# playA.net
KiCad netlist of a schematic drawn in Altium Designer
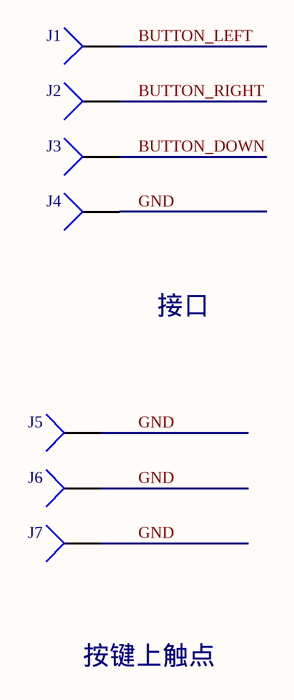
[diagram p0: playA.SchDoc]

(export (version "E")
  (design (tool "Eeschema 10.0.6"))
  (components
    (comp (ref "J1")
      (value "PAD")
      (footprint "LINK_PAD")
      (description "Socket")
      (fields (field (name "PUBLISHER") "Altium Limited"))
      (libsource (lib "Miscellaneous Connectors") (part "Socket"))
    )
    (comp (ref "J2")
      (value "PAD")
      (footprint "LINK_PAD")
      (description "Socket")
      (fields (field (name "PUBLISHER") "Altium Limited"))
      (libsource (lib "Miscellaneous Connectors") (part "Socket"))
    )
    (comp (ref "J3")
      (value "PAD")
      (footprint "LINK_PAD")
      (description "Socket")
      (fields (field (name "PUBLISHER") "Altium Limited"))
      (libsource (lib "Miscellaneous Connectors") (part "Socket"))
    )
    (comp (ref "J4")
      (value "PAD")
      (footprint "LINK_PAD")
      (description "Socket")
      (fields (field (name "PUBLISHER") "Altium Limited"))
      (libsource (lib "Miscellaneous Connectors") (part "Socket"))
    )
    (comp (ref "J5")
      (value "PAD")
      (footprint "Button_Pad")
      (description "Socket")
      (fields (field (name "PUBLISHER") "Altium Limited"))
      (libsource (lib "Miscellaneous Connectors") (part "Socket"))
    )
    (comp (ref "J6")
      (value "PAD")
      (footprint "Button_Pad")
      (description "Socket")
      (fields (field (name "PUBLISHER") "Altium Limited"))
      (libsource (lib "Miscellaneous Connectors") (part "Socket"))
    )
    (comp (ref "J7")
      (value "PAD")
      (footprint "Button_Pad")
      (description "Socket")
      (fields (field (name "PUBLISHER") "Altium Limited"))
      (libsource (lib "Miscellaneous Connectors") (part "Socket"))
    )
  )
  (nets
    (net (code "1") (name "/BUTTON_DOWN") (class "Default")
      (node (ref "J3") (pin "1") (pinfunction "1_1") (pintype "passive"))
    )
    (net (code "2") (name "/BUTTON_LEFT") (class "Default")
      (node (ref "J1") (pin "1") (pinfunction "1_1") (pintype "passive"))
    )
    (net (code "3") (name "/BUTTON_RIGHT") (class "Default")
      (node (ref "J2") (pin "1") (pinfunction "1_1") (pintype "passive"))
    )
    (net (code "4") (name "/GND") (class "Default")
      (node (ref "J4") (pin "1") (pinfunction "1_1") (pintype "passive"))
      (node (ref "J5") (pin "1") (pinfunction "1_1") (pintype "passive"))
      (node (ref "J6") (pin "1") (pinfunction "1_1") (pintype "passive"))
      (node (ref "J7") (pin "1") (pinfunction "1_1") (pintype "passive"))
    )
  )
)
